# -9V_PSU.net
KiCad netlist of a schematic drawn in EAGLE
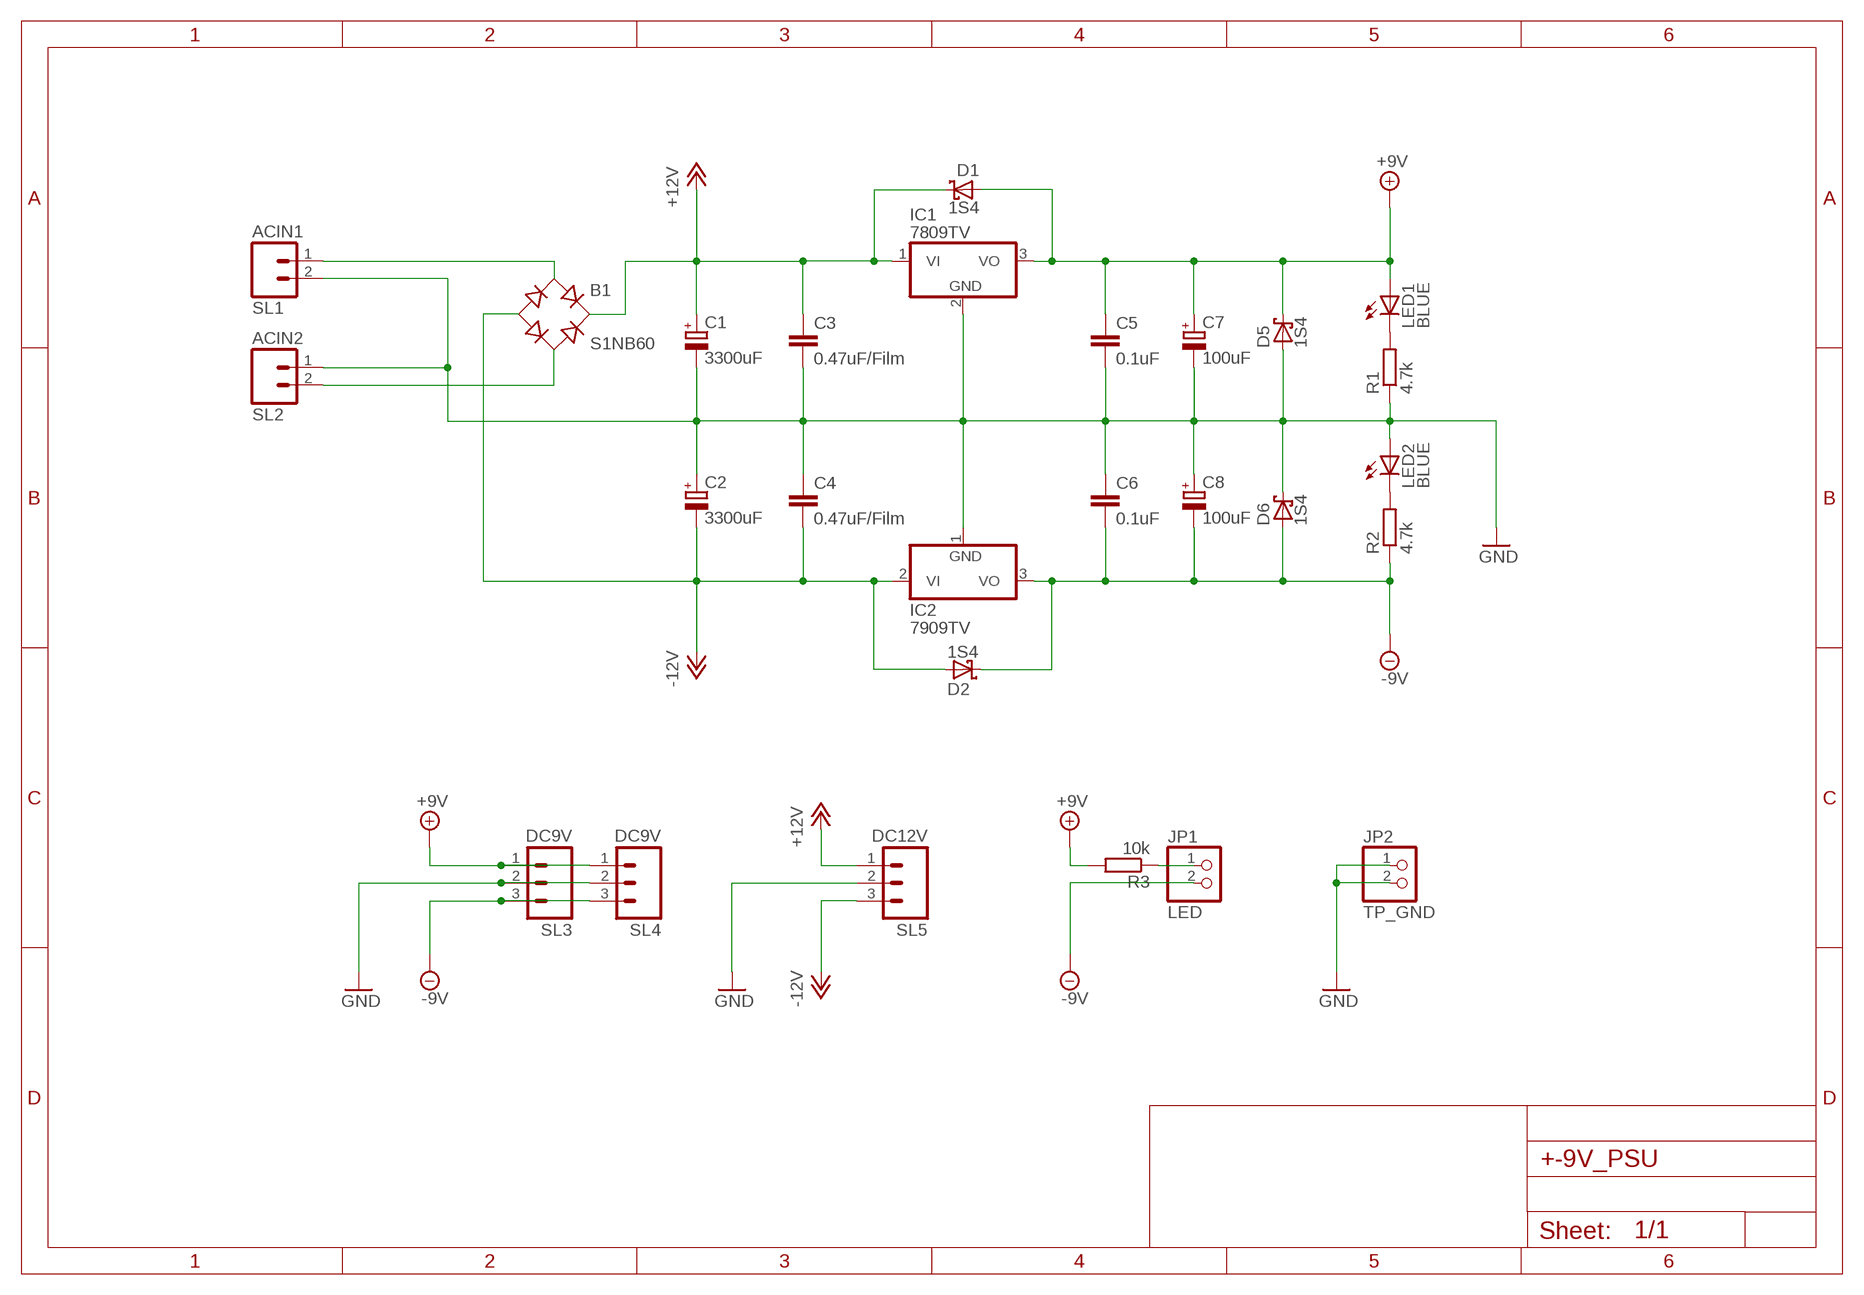
[diagram p0: schematic, sheet 1]

(export (version "E")
  (design (tool "Eeschema 10.0.6"))
  (components
    (comp (ref "B1")
      (value "S1NB60")
      (footprint "eagle-import:B-DIL")
      (libsource (lib "eagle-import") (part "B-DIL"))
    )
    (comp (ref "C1")
      (value "3300uF")
      (footprint "eagle-import:EB25D")
      (libsource (lib "eagle-import") (part "CPOL-EUE10-25"))
    )
    (comp (ref "C2")
      (value "3300uF")
      (footprint "eagle-import:EB25D")
      (libsource (lib "eagle-import") (part "CPOL-EUE10-25"))
    )
    (comp (ref "C3")
      (value "0.47uF/Film")
      (footprint "eagle-import:C050-045X075")
      (libsource (lib "eagle-import") (part "C-EU050-045X075"))
    )
    (comp (ref "C4")
      (value "0.47uF/Film")
      (footprint "eagle-import:C050-045X075")
      (libsource (lib "eagle-import") (part "C-EU050-045X075"))
    )
    (comp (ref "C5")
      (value "0.1uF")
      (footprint "eagle-import:C025-024X044")
      (libsource (lib "eagle-import") (part "C-EU025-024X044"))
    )
    (comp (ref "C6")
      (value "0.1uF")
      (footprint "eagle-import:C025-024X044")
      (libsource (lib "eagle-import") (part "C-EU025-024X044"))
    )
    (comp (ref "C7")
      (value "100uF")
      (footprint "eagle-import:SANYO-OSCON_C6")
      (libsource (lib "eagle-import") (part "CPOL-EUSANYO_C6"))
    )
    (comp (ref "C8")
      (value "100uF")
      (footprint "eagle-import:SANYO-OSCON_C6")
      (libsource (lib "eagle-import") (part "CPOL-EUSANYO_C6"))
    )
    (comp (ref "D1")
      (value "1S4")
      (footprint "eagle-import:DO35-7")
      (libsource (lib "eagle-import") (part "SCHOTTKY-DIODEDO35-7"))
    )
    (comp (ref "D2")
      (value "1S4")
      (footprint "eagle-import:DO35-7")
      (libsource (lib "eagle-import") (part "SCHOTTKY-DIODEDO35-7"))
    )
    (comp (ref "D5")
      (value "1S4")
      (footprint "eagle-import:DO35-7")
      (libsource (lib "eagle-import") (part "SCHOTTKY-DIODEDO35-7"))
    )
    (comp (ref "D6")
      (value "1S4")
      (footprint "eagle-import:DO35-7")
      (libsource (lib "eagle-import") (part "SCHOTTKY-DIODEDO35-7"))
    )
    (comp (ref "IC1")
      (value "7809TV")
      (footprint "eagle-import:TO220V")
      (libsource (lib "eagle-import") (part "78TV05"))
    )
    (comp (ref "IC2")
      (value "7909TV")
      (footprint "eagle-import:TO220V")
      (libsource (lib "eagle-import") (part "7905TV"))
    )
    (comp (ref "JP1")
      (value "LED")
      (footprint "eagle-import:1X02")
      (libsource (lib "eagle-import") (part "PINHD-1X2"))
    )
    (comp (ref "JP2")
      (value "TP_GND")
      (footprint "eagle-import:1X02")
      (libsource (lib "eagle-import") (part "PINHD-1X2"))
    )
    (comp (ref "LED1")
      (value "BLUE")
      (footprint "eagle-import:LED3MM")
      (libsource (lib "eagle-import") (part "LED3MM"))
    )
    (comp (ref "LED2")
      (value "BLUE")
      (footprint "eagle-import:LED3MM")
      (libsource (lib "eagle-import") (part "LED3MM"))
    )
    (comp (ref "R1")
      (value "4.7k")
      (footprint "eagle-import:0207_7")
      (libsource (lib "eagle-import") (part "R-EU_0207/7"))
    )
    (comp (ref "R2")
      (value "4.7k")
      (footprint "eagle-import:0207_7")
      (libsource (lib "eagle-import") (part "R-EU_0207/7"))
    )
    (comp (ref "R3")
      (value "10k")
      (footprint "eagle-import:0207_7")
      (libsource (lib "eagle-import") (part "R-EU_0207/7"))
    )
    (comp (ref "SL1")
      (value "ACIN1")
      (footprint "eagle-import:02P")
      (libsource (lib "eagle-import") (part "M02"))
    )
    (comp (ref "SL2")
      (value "ACIN2")
      (footprint "eagle-import:02P")
      (libsource (lib "eagle-import") (part "M02"))
    )
    (comp (ref "SL3")
      (value "DC9V")
      (footprint "eagle-import:03P")
      (libsource (lib "eagle-import") (part "M03"))
    )
    (comp (ref "SL4")
      (value "DC9V")
      (footprint "eagle-import:03P")
      (libsource (lib "eagle-import") (part "M03"))
    )
    (comp (ref "SL5")
      (value "DC12V")
      (footprint "eagle-import:03P")
      (libsource (lib "eagle-import") (part "M03"))
    )
  )
  (nets
    (net (code "1") (name "+9V") (class "Default")
      (node (ref "C5") (pin "1") (pinfunction "1_1") (pintype "passive"))
      (node (ref "C7") (pin "+") (pinfunction "+_+") (pintype "passive"))
      (node (ref "D1") (pin "A") (pinfunction "A_A") (pintype "passive"))
      (node (ref "D5") (pin "C") (pinfunction "C_C") (pintype "passive"))
      (node (ref "IC1") (pin "3") (pinfunction "VO_3") (pintype "passive"))
      (node (ref "LED1") (pin "A") (pinfunction "A_A") (pintype "passive"))
      (node (ref "R3") (pin "2") (pinfunction "2_2") (pintype "passive"))
      (node (ref "SL3") (pin "1") (pinfunction "1_1") (pintype "passive"))
      (node (ref "SL4") (pin "1") (pinfunction "1_1") (pintype "passive"))
    )
    (net (code "2") (name "+12V") (class "Default")
      (node (ref "B1") (pin "+") (pinfunction "+_+") (pintype "passive"))
      (node (ref "C1") (pin "+") (pinfunction "+_+") (pintype "passive"))
      (node (ref "C3") (pin "1") (pinfunction "1_1") (pintype "passive"))
      (node (ref "D1") (pin "C") (pinfunction "C_C") (pintype "passive"))
      (node (ref "IC1") (pin "1") (pinfunction "VI_1") (pintype "input"))
      (node (ref "SL5") (pin "1") (pinfunction "1_1") (pintype "passive"))
    )
    (net (code "3") (name "-9V") (class "Default")
      (node (ref "C6") (pin "2") (pinfunction "2_2") (pintype "passive"))
      (node (ref "C8") (pin "-") (pinfunction "-_-") (pintype "passive"))
      (node (ref "D2") (pin "C") (pinfunction "C_C") (pintype "passive"))
      (node (ref "D6") (pin "A") (pinfunction "A_A") (pintype "passive"))
      (node (ref "IC2") (pin "3") (pinfunction "VO_3") (pintype "passive"))
      (node (ref "JP1") (pin "2") (pinfunction "2_2") (pintype "passive"))
      (node (ref "R2") (pin "1") (pinfunction "1_1") (pintype "passive"))
      (node (ref "SL3") (pin "3") (pinfunction "3_3") (pintype "passive"))
      (node (ref "SL4") (pin "3") (pinfunction "3_3") (pintype "passive"))
    )
    (net (code "4") (name "-12V") (class "Default")
      (node (ref "B1") (pin "-") (pinfunction "-_-") (pintype "passive"))
      (node (ref "C2") (pin "-") (pinfunction "-_-") (pintype "passive"))
      (node (ref "C4") (pin "2") (pinfunction "2_2") (pintype "passive"))
      (node (ref "D2") (pin "A") (pinfunction "A_A") (pintype "passive"))
      (node (ref "IC2") (pin "2") (pinfunction "VI_2") (pintype "input"))
      (node (ref "SL5") (pin "3") (pinfunction "3_3") (pintype "passive"))
    )
    (net (code "5") (name "GND") (class "Default")
      (node (ref "C1") (pin "-") (pinfunction "-_-") (pintype "passive"))
      (node (ref "C2") (pin "+") (pinfunction "+_+") (pintype "passive"))
      (node (ref "C3") (pin "2") (pinfunction "2_2") (pintype "passive"))
      (node (ref "C4") (pin "1") (pinfunction "1_1") (pintype "passive"))
      (node (ref "C5") (pin "2") (pinfunction "2_2") (pintype "passive"))
      (node (ref "C6") (pin "1") (pinfunction "1_1") (pintype "passive"))
      (node (ref "C7") (pin "-") (pinfunction "-_-") (pintype "passive"))
      (node (ref "C8") (pin "+") (pinfunction "+_+") (pintype "passive"))
      (node (ref "D5") (pin "A") (pinfunction "A_A") (pintype "passive"))
      (node (ref "D6") (pin "C") (pinfunction "C_C") (pintype "passive"))
      (node (ref "IC1") (pin "2") (pinfunction "GND_2") (pintype "passive"))
      (node (ref "IC2") (pin "1") (pinfunction "GND_1") (pintype "passive"))
      (node (ref "JP2") (pin "1") (pinfunction "1_1") (pintype "passive"))
      (node (ref "JP2") (pin "2") (pinfunction "2_2") (pintype "passive"))
      (node (ref "LED2") (pin "A") (pinfunction "A_A") (pintype "passive"))
      (node (ref "R1") (pin "1") (pinfunction "1_1") (pintype "passive"))
      (node (ref "SL1") (pin "2") (pinfunction "2_2") (pintype "passive"))
      (node (ref "SL2") (pin "1") (pinfunction "1_1") (pintype "passive"))
      (node (ref "SL3") (pin "2") (pinfunction "2_2") (pintype "passive"))
      (node (ref "SL4") (pin "2") (pinfunction "2_2") (pintype "passive"))
      (node (ref "SL5") (pin "2") (pinfunction "2_2") (pintype "passive"))
    )
    (net (code "6") (name "Net-(B1-PadAC1)") (class "Default")
      (node (ref "B1") (pin "AC1") (pinfunction "AC1_AC1") (pintype "passive"))
      (node (ref "SL1") (pin "1") (pinfunction "1_1") (pintype "passive"))
    )
    (net (code "7") (name "Net-(B1-PadAC2)") (class "Default")
      (node (ref "B1") (pin "AC2") (pinfunction "AC2_AC2") (pintype "passive"))
      (node (ref "SL2") (pin "2") (pinfunction "2_2") (pintype "passive"))
    )
    (net (code "8") (name "Net-(JP1-Pad1)") (class "Default")
      (node (ref "JP1") (pin "1") (pinfunction "1_1") (pintype "passive"))
      (node (ref "R3") (pin "1") (pinfunction "1_1") (pintype "passive"))
    )
    (net (code "9") (name "Net-(LED1-C)") (class "Default")
      (node (ref "LED1") (pin "K") (pinfunction "C_K") (pintype "passive"))
      (node (ref "R1") (pin "2") (pinfunction "2_2") (pintype "passive"))
    )
    (net (code "10") (name "Net-(LED2-C)") (class "Default")
      (node (ref "LED2") (pin "K") (pinfunction "C_K") (pintype "passive"))
      (node (ref "R2") (pin "2") (pinfunction "2_2") (pintype "passive"))
    )
  )
)
